# openSX70-dongle_SEEED_v52-V.net
KiCad netlist of a schematic drawn in EAGLE
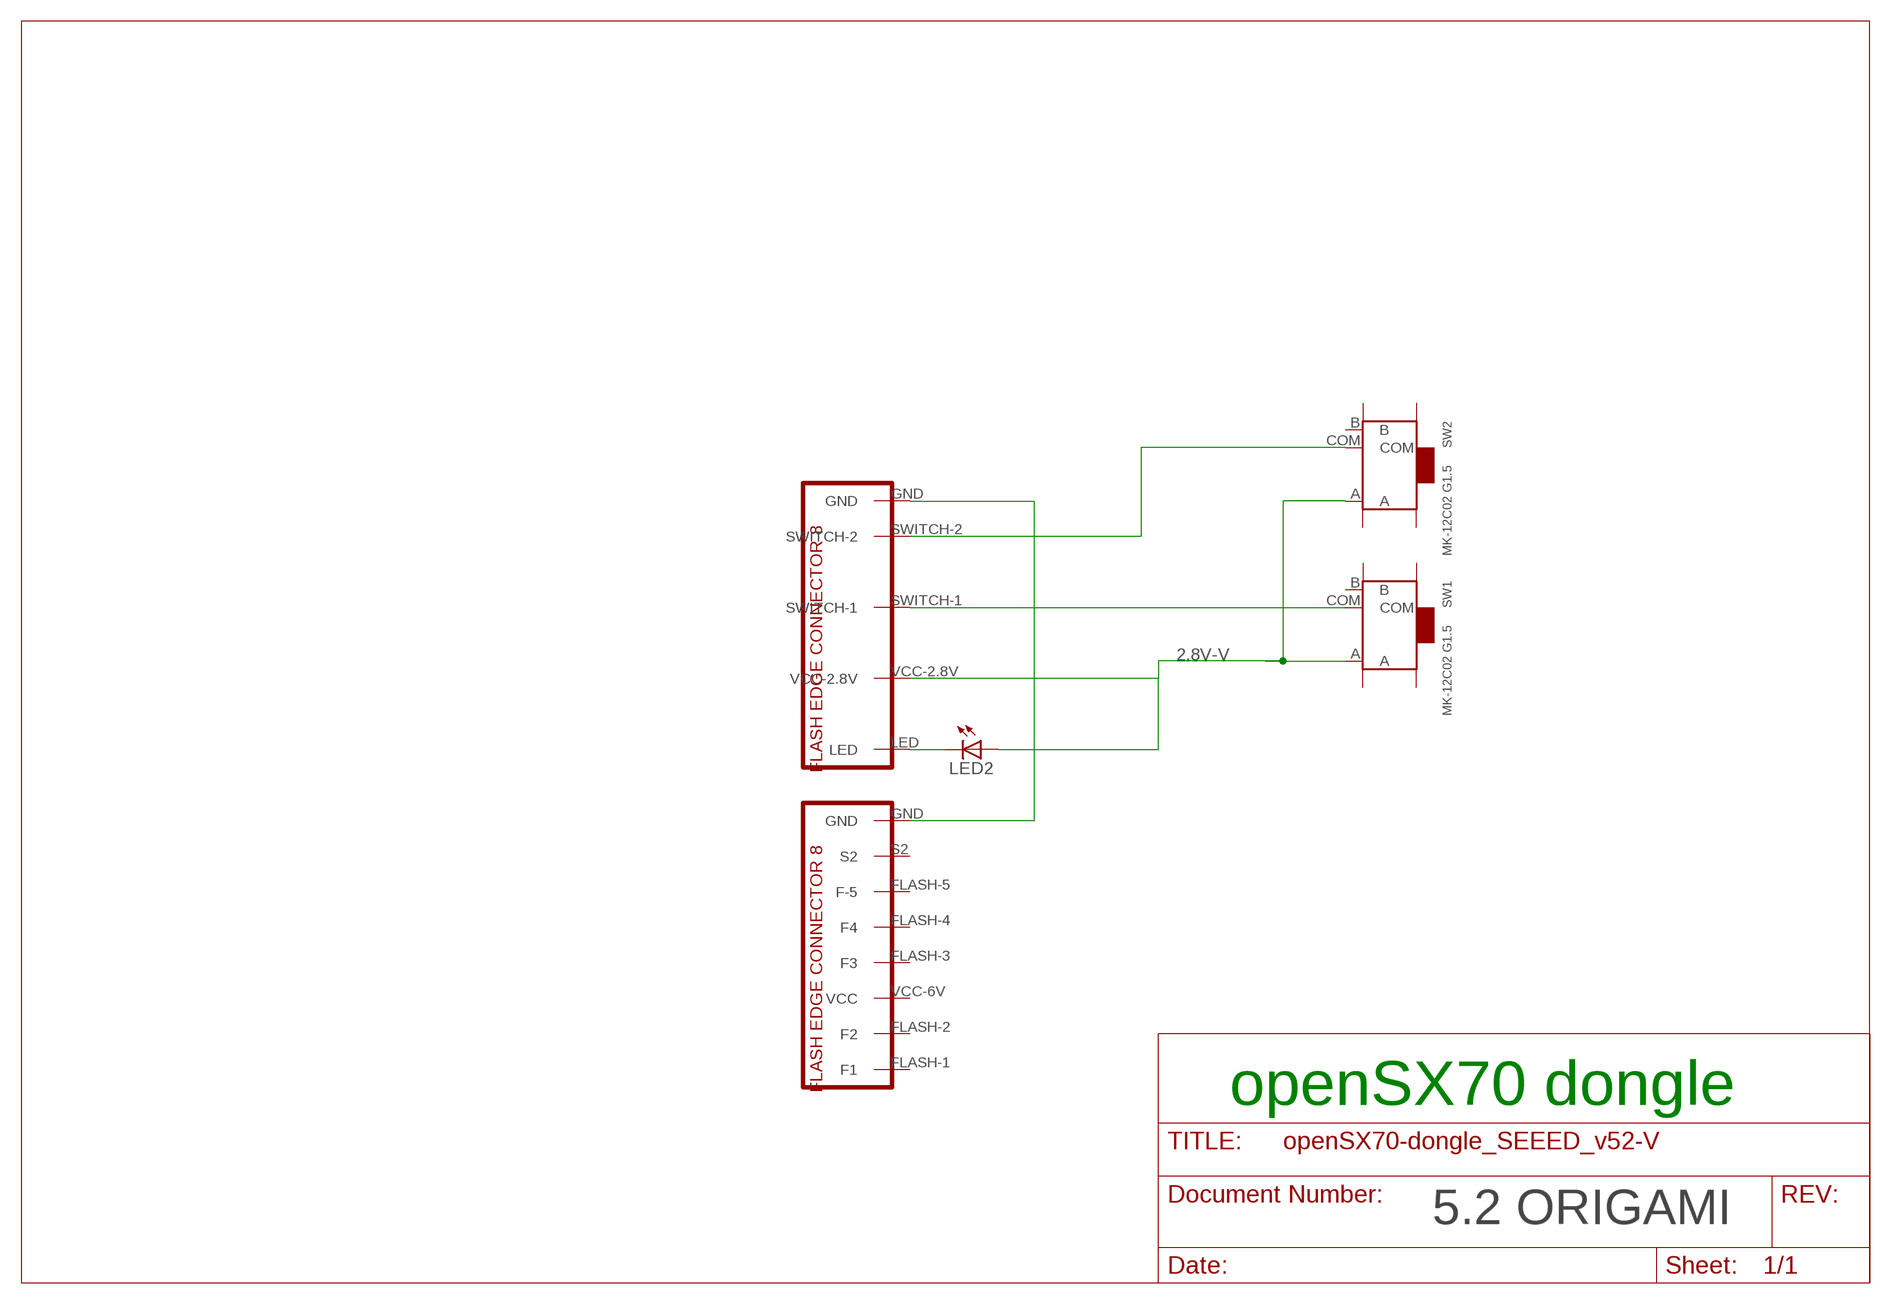
[diagram p0: schematic, sheet 1]

(export (version "E")
  (design (tool "Eeschema 10.0.6"))
  (components
    (comp (ref "LED2")
      (value "LEDCHIP-LED0805")
      (footprint "eagle-import:CHIP-LED0805")
      (libsource (lib "eagle-import") (part "LEDCHIP-LED0805"))
    )
    (comp (ref "SW1")
      (value "MK-12C02 G1.5")
      (footprint "eagle-import:SW7-SMD-L6.7X2.7X3.2MM")
      (libsource (lib "eagle-import") (part "SMD-TOGGLE-SWITCH-ON-ON(3+4P-6.7X2.7MM)"))
    )
    (comp (ref "SW2")
      (value "MK-12C02 G1.5")
      (footprint "eagle-import:SW7-SMD-L6.7X2.7X3.2MM")
      (libsource (lib "eagle-import") (part "SMD-TOGGLE-SWITCH-ON-ON(3+4P-6.7X2.7MM)"))
    )
    (comp (ref "U$1")
      (value "FLASH-BRIDGE-SW1-SW2-LED-SMALL")
      (footprint "eagle-import:FLASH-8-BRIDGE-SW1-SW2-LED-SMALL")
      (libsource (lib "eagle-import") (part "FLASH-BRIDGE-SW1-SW2-LED-SMALL"))
    )
    (comp (ref "U$2")
      (value "SX70-FLASH-EDGE8-MALE-LONG")
      (footprint "eagle-import:SX70-FLASH-EDGE8-2")
      (libsource (lib "eagle-import") (part "SX70-FLASH-EDGE8-MALE-LONG"))
    )
  )
  (nets
    (net (code "1") (name "/2.8V-V") (class "Default")
      (node (ref "LED2") (pin "A") (pinfunction "A_A") (pintype "passive"))
      (node (ref "SW1") (pin "A") (pinfunction "A_A") (pintype "bidirectional"))
      (node (ref "SW2") (pin "A") (pinfunction "A_A") (pintype "bidirectional"))
      (node (ref "U$1") (pin "VCC-2.8V") (pinfunction "VCC-2.8V_VCC-2.8V") (pintype "bidirectional"))
    )
    (net (code "2") (name "Net-(LED2-PadC)") (class "Default")
      (node (ref "LED2") (pin "C") (pinfunction "C_C") (pintype "passive"))
      (node (ref "U$1") (pin "LED") (pinfunction "LED_LED") (pintype "bidirectional"))
    )
    (net (code "3") (name "Net-(SW1-PadCOM)") (class "Default")
      (node (ref "SW1") (pin "COM") (pinfunction "COM_COM") (pintype "bidirectional"))
      (node (ref "U$1") (pin "SWITCH-1") (pinfunction "SWITCH-1_SWITCH-1") (pintype "bidirectional"))
    )
    (net (code "4") (name "Net-(SW2-PadCOM)") (class "Default")
      (node (ref "SW2") (pin "COM") (pinfunction "COM_COM") (pintype "bidirectional"))
      (node (ref "U$1") (pin "SWITCH-2") (pinfunction "SWITCH-2_SWITCH-2") (pintype "bidirectional"))
    )
    (net (code "5") (name "Net-(U$1-PadGND)") (class "Default")
      (node (ref "U$1") (pin "GND") (pinfunction "GND_GND") (pintype "bidirectional"))
      (node (ref "U$2") (pin "GND") (pinfunction "GND_GND") (pintype "bidirectional"))
    )
    (net (code "6") (name "unconnected-(SW1-PadB)") (class "Default")
      (node (ref "SW1") (pin "B") (pinfunction "B_B") (pintype "bidirectional"))
    )
    (net (code "7") (name "unconnected-(SW1-PadSS1)") (class "Default")
      (node (ref "SW1") (pin "SS1") (pinfunction "SS1_SS1") (pintype "bidirectional"))
    )
    (net (code "8") (name "unconnected-(SW1-PadSS2)") (class "Default")
      (node (ref "SW1") (pin "SS2") (pinfunction "SS2_SS2") (pintype "bidirectional"))
    )
    (net (code "9") (name "unconnected-(SW1-PadSS3)") (class "Default")
      (node (ref "SW1") (pin "SS3") (pinfunction "SS3_SS3") (pintype "bidirectional"))
    )
    (net (code "10") (name "unconnected-(SW1-PadSS4)") (class "Default")
      (node (ref "SW1") (pin "SS4") (pinfunction "SS4_SS4") (pintype "bidirectional"))
    )
    (net (code "11") (name "unconnected-(SW2-PadB)") (class "Default")
      (node (ref "SW2") (pin "B") (pinfunction "B_B") (pintype "bidirectional"))
    )
    (net (code "12") (name "unconnected-(SW2-PadSS1)") (class "Default")
      (node (ref "SW2") (pin "SS1") (pinfunction "SS1_SS1") (pintype "bidirectional"))
    )
    (net (code "13") (name "unconnected-(SW2-PadSS2)") (class "Default")
      (node (ref "SW2") (pin "SS2") (pinfunction "SS2_SS2") (pintype "bidirectional"))
    )
    (net (code "14") (name "unconnected-(SW2-PadSS3)") (class "Default")
      (node (ref "SW2") (pin "SS3") (pinfunction "SS3_SS3") (pintype "bidirectional"))
    )
    (net (code "15") (name "unconnected-(SW2-PadSS4)") (class "Default")
      (node (ref "SW2") (pin "SS4") (pinfunction "SS4_SS4") (pintype "bidirectional"))
    )
    (net (code "16") (name "unconnected-(U$2-F-5-PadFLASH-5)") (class "Default")
      (node (ref "U$2") (pin "FLASH-5") (pinfunction "F-5_FLASH-5") (pintype "bidirectional"))
    )
    (net (code "17") (name "unconnected-(U$2-F1-PadFLASH-1)") (class "Default")
      (node (ref "U$2") (pin "FLASH-1") (pinfunction "F1_FLASH-1") (pintype "bidirectional"))
    )
    (net (code "18") (name "unconnected-(U$2-F2-PadFLASH-2)") (class "Default")
      (node (ref "U$2") (pin "FLASH-2") (pinfunction "F2_FLASH-2") (pintype "bidirectional"))
    )
    (net (code "19") (name "unconnected-(U$2-F3-PadFLASH-3)") (class "Default")
      (node (ref "U$2") (pin "FLASH-3") (pinfunction "F3_FLASH-3") (pintype "bidirectional"))
    )
    (net (code "20") (name "unconnected-(U$2-F4-PadFLASH-4)") (class "Default")
      (node (ref "U$2") (pin "FLASH-4") (pinfunction "F4_FLASH-4") (pintype "bidirectional"))
    )
    (net (code "21") (name "unconnected-(U$2-PadS2)") (class "Default")
      (node (ref "U$2") (pin "S2") (pinfunction "S2_S2") (pintype "bidirectional"))
    )
    (net (code "22") (name "unconnected-(U$2-VCC-PadVCC-6V)") (class "Default")
      (node (ref "U$2") (pin "VCC-6V") (pinfunction "VCC_VCC-6V") (pintype "bidirectional"))
    )
  )
)
